# MCU_v2.net
KiCad netlist of a schematic drawn in Altium Designer
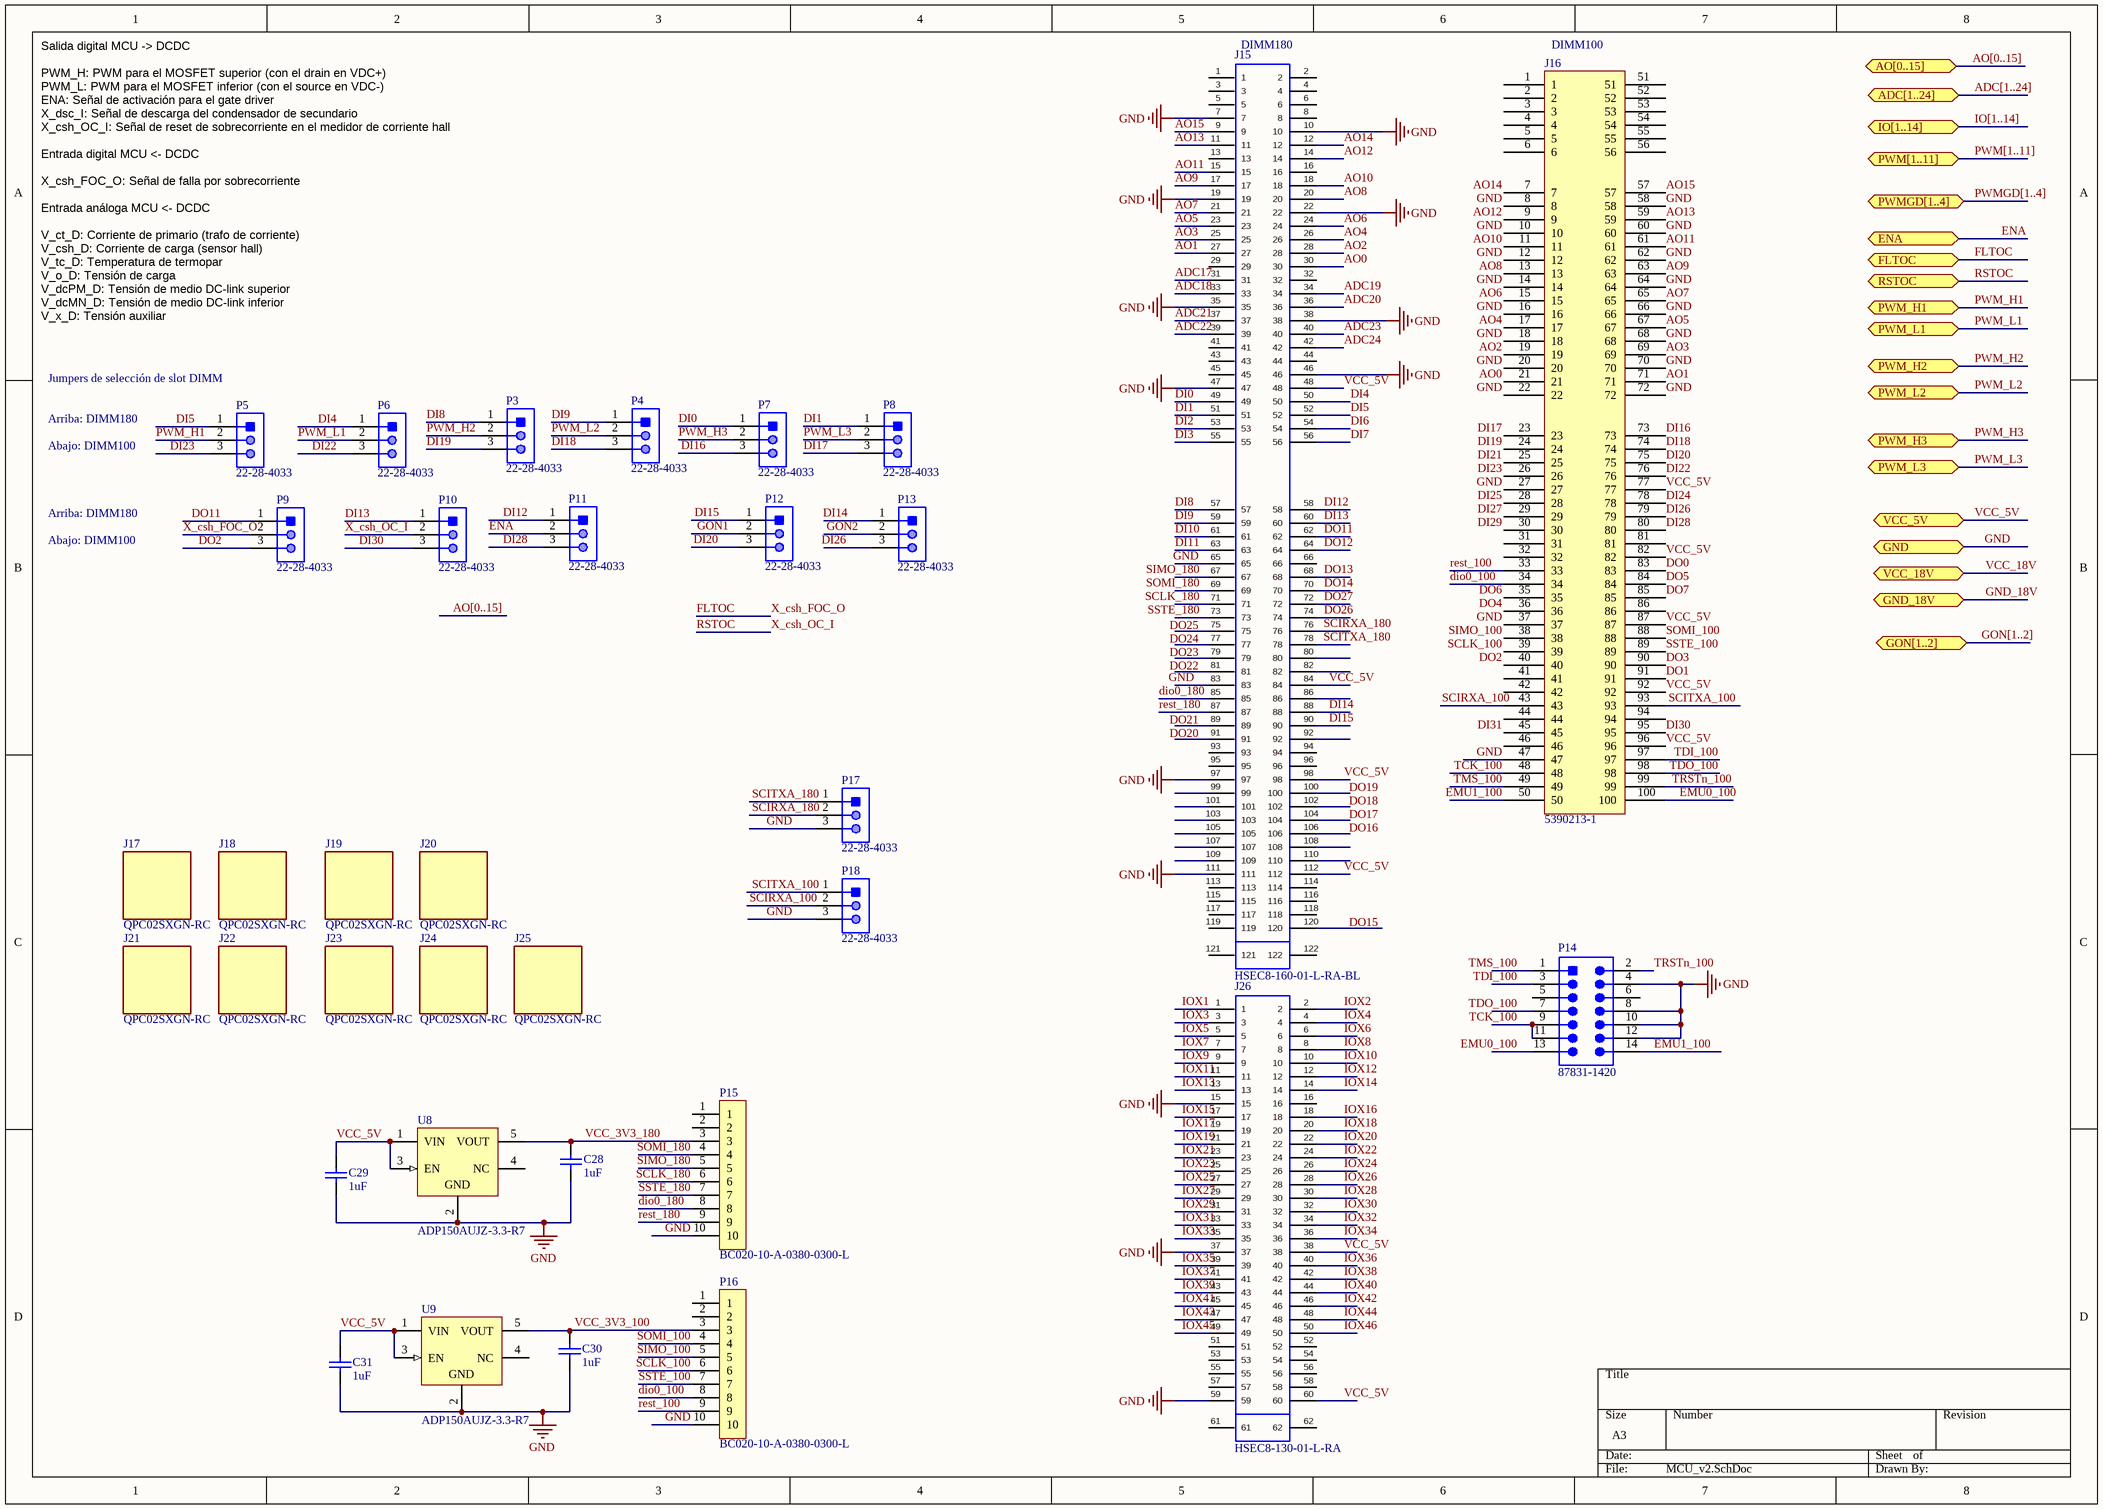
[diagram p0: MCU_v2.SchDoc]

(export (version "E")
  (design (tool "Eeschema 10.0.6"))
  (components
    (comp (ref "C28")
      (value "1uF")
      (footprint "CAPC0603(1608)100_N")
      (description "CAP 1uF 50V ±20% 0603 (1608 Metric) Thickness 1mm SMD")
      (fields (field (name "TOLERANCE") "Â±20%") (field (name "Comment") "CAP 1uF 50V 0603(1608)"))
      (libsource (lib "Altium Content Vault") (part "CAP"))
    )
    (comp (ref "C29")
      (value "1uF")
      (footprint "CAPC0603(1608)100_N")
      (description "CAP 1uF 50V ±20% 0603 (1608 Metric) Thickness 1mm SMD")
      (fields (field (name "TOLERANCE") "Â±20%") (field (name "Comment") "CAP 1uF 50V 0603(1608)"))
      (libsource (lib "Altium Content Vault") (part "CAP"))
    )
    (comp (ref "C30")
      (value "1uF")
      (footprint "CAPC0603(1608)100_N")
      (description "CAP 1uF 50V ±20% 0603 (1608 Metric) Thickness 1mm SMD")
      (fields (field (name "TOLERANCE") "Â±20%") (field (name "Comment") "CAP 1uF 50V 0603(1608)"))
      (libsource (lib "Altium Content Vault") (part "CAP"))
    )
    (comp (ref "C31")
      (value "1uF")
      (footprint "CAPC0603(1608)100_N")
      (description "CAP 1uF 50V ±20% 0603 (1608 Metric) Thickness 1mm SMD")
      (fields (field (name "TOLERANCE") "Â±20%") (field (name "Comment") "CAP 1uF 50V 0603(1608)"))
      (libsource (lib "Altium Content Vault") (part "CAP"))
    )
    (comp (ref "J15")
      (value "HSEC8-160-01-L-RA-BL")
      (footprint "HSEC8-160-01-L-RA-BL")
      (description "Standard Card Edge Connectors 0.80 mm Edge Rate High-Speed Edge Card Connector, Vertical")
      (fields (field (name "MANUFACTURER") "Samtec"))
      (libsource (lib "Altium_Library_POWERLAB") (part "HSEC8-160-01-L-RA-BL"))
    )
    (comp (ref "J16")
      (value "5390213-1")
      (footprint "TE_5390213-1")
      (description "100 Position DIMM DRAM Socket Through Hole")
      (fields (field (name "MF") "TE Connectivity"))
      (libsource (lib "Altium_Library_POWERLAB") (part "5390213-1"))
    )
    (comp (ref "J17")
      (value "QPC02SXGN-RC")
      (footprint "FP-QPC02SXGN-RC-MFG")
      (description "CONN JUMPER SHORTING .100\" GOLD")
      (fields
        (field (name "MANUFACTURER") "Sullins")
        (field (name "OCTOPART") "https://octopart.com/qpc02sxgn-rc-sullins-19878795")
      )
      (libsource (lib "Altium Content Vault") (part "87292ac8601c6cf2061292f5bede09e"))
    )
    (comp (ref "J18")
      (value "QPC02SXGN-RC")
      (footprint "FP-QPC02SXGN-RC-MFG")
      (description "CONN JUMPER SHORTING .100\" GOLD")
      (fields
        (field (name "MANUFACTURER") "Sullins")
        (field (name "OCTOPART") "https://octopart.com/qpc02sxgn-rc-sullins-19878795")
      )
      (libsource (lib "Altium Content Vault") (part "87292ac8601c6cf2061292f5bede09e"))
    )
    (comp (ref "J19")
      (value "QPC02SXGN-RC")
      (footprint "FP-QPC02SXGN-RC-MFG")
      (description "CONN JUMPER SHORTING .100\" GOLD")
      (fields
        (field (name "MANUFACTURER") "Sullins")
        (field (name "OCTOPART") "https://octopart.com/qpc02sxgn-rc-sullins-19878795")
      )
      (libsource (lib "Altium Content Vault") (part "87292ac8601c6cf2061292f5bede09e"))
    )
    (comp (ref "J20")
      (value "QPC02SXGN-RC")
      (footprint "FP-QPC02SXGN-RC-MFG")
      (description "CONN JUMPER SHORTING .100\" GOLD")
      (fields
        (field (name "MANUFACTURER") "Sullins")
        (field (name "OCTOPART") "https://octopart.com/qpc02sxgn-rc-sullins-19878795")
      )
      (libsource (lib "Altium Content Vault") (part "87292ac8601c6cf2061292f5bede09e"))
    )
    (comp (ref "J21")
      (value "QPC02SXGN-RC")
      (footprint "FP-QPC02SXGN-RC-MFG")
      (description "CONN JUMPER SHORTING .100\" GOLD")
      (fields
        (field (name "MANUFACTURER") "Sullins")
        (field (name "OCTOPART") "https://octopart.com/qpc02sxgn-rc-sullins-19878795")
      )
      (libsource (lib "Altium Content Vault") (part "87292ac8601c6cf2061292f5bede09e"))
    )
    (comp (ref "J22")
      (value "QPC02SXGN-RC")
      (footprint "FP-QPC02SXGN-RC-MFG")
      (description "CONN JUMPER SHORTING .100\" GOLD")
      (fields
        (field (name "MANUFACTURER") "Sullins")
        (field (name "OCTOPART") "https://octopart.com/qpc02sxgn-rc-sullins-19878795")
      )
      (libsource (lib "Altium Content Vault") (part "87292ac8601c6cf2061292f5bede09e"))
    )
    (comp (ref "J23")
      (value "QPC02SXGN-RC")
      (footprint "FP-QPC02SXGN-RC-MFG")
      (description "CONN JUMPER SHORTING .100\" GOLD")
      (fields
        (field (name "MANUFACTURER") "Sullins")
        (field (name "OCTOPART") "https://octopart.com/qpc02sxgn-rc-sullins-19878795")
      )
      (libsource (lib "Altium Content Vault") (part "87292ac8601c6cf2061292f5bede09e"))
    )
    (comp (ref "J24")
      (value "QPC02SXGN-RC")
      (footprint "FP-QPC02SXGN-RC-MFG")
      (description "CONN JUMPER SHORTING .100\" GOLD")
      (fields
        (field (name "MANUFACTURER") "Sullins")
        (field (name "OCTOPART") "https://octopart.com/qpc02sxgn-rc-sullins-19878795")
      )
      (libsource (lib "Altium Content Vault") (part "87292ac8601c6cf2061292f5bede09e"))
    )
    (comp (ref "J25")
      (value "QPC02SXGN-RC")
      (footprint "FP-QPC02SXGN-RC-MFG")
      (description "CONN JUMPER SHORTING .100\" GOLD")
      (fields
        (field (name "MANUFACTURER") "Sullins")
        (field (name "OCTOPART") "https://octopart.com/qpc02sxgn-rc-sullins-19878795")
      )
      (libsource (lib "Altium Content Vault") (part "87292ac8601c6cf2061292f5bede09e"))
    )
    (comp (ref "J26")
      (value "HSEC8-130-01-L-RA")
      (footprint "HSEC8-130-01-L-RA")
      (description "SAMTEC - HSEC8-130-01-L-RA - CARD EDGE CONN, DUAL SIDE, 60POS, SMD")
      (fields (field (name "MANUFACTURER") "Samtec"))
      (libsource (lib "Altium_Library_POWERLAB") (part "HSEC8-130-01-L-RA"))
    )
    (comp (ref "P3")
      (value "22-28-4033")
      (footprint "MOLX-22-28-4033_V")
      (description "Male Header, Pitch 2.54 mm, 1 x 3 Position, Height 8.38 mm, Tail Length 3.18 mm, RoHS, Bulk")
      (fields (field (name "MANUFACTURER") "Molex"))
      (libsource (lib "Altium Content Vault") (part "CN-1P-M-R3"))
    )
    (comp (ref "P4")
      (value "22-28-4033")
      (footprint "MOLX-22-28-4033_V")
      (description "Male Header, Pitch 2.54 mm, 1 x 3 Position, Height 8.38 mm, Tail Length 3.18 mm, RoHS, Bulk")
      (fields (field (name "MANUFACTURER") "Molex"))
      (libsource (lib "Altium Content Vault") (part "CN-1P-M-R3"))
    )
    (comp (ref "P5")
      (value "22-28-4033")
      (footprint "MOLX-22-28-4033_V")
      (description "Male Header, Pitch 2.54 mm, 1 x 3 Position, Height 8.38 mm, Tail Length 3.18 mm, RoHS, Bulk")
      (fields (field (name "MANUFACTURER") "Molex"))
      (libsource (lib "Altium Content Vault") (part "CN-1P-M-R3"))
    )
    (comp (ref "P6")
      (value "22-28-4033")
      (footprint "MOLX-22-28-4033_V")
      (description "Male Header, Pitch 2.54 mm, 1 x 3 Position, Height 8.38 mm, Tail Length 3.18 mm, RoHS, Bulk")
      (fields (field (name "MANUFACTURER") "Molex"))
      (libsource (lib "Altium Content Vault") (part "CN-1P-M-R3"))
    )
    (comp (ref "P7")
      (value "22-28-4033")
      (footprint "MOLX-22-28-4033_V")
      (description "Male Header, Pitch 2.54 mm, 1 x 3 Position, Height 8.38 mm, Tail Length 3.18 mm, RoHS, Bulk")
      (fields (field (name "MANUFACTURER") "Molex"))
      (libsource (lib "Altium Content Vault") (part "CN-1P-M-R3"))
    )
    (comp (ref "P8")
      (value "22-28-4033")
      (footprint "MOLX-22-28-4033_V")
      (description "Male Header, Pitch 2.54 mm, 1 x 3 Position, Height 8.38 mm, Tail Length 3.18 mm, RoHS, Bulk")
      (fields (field (name "MANUFACTURER") "Molex"))
      (libsource (lib "Altium Content Vault") (part "CN-1P-M-R3"))
    )
    (comp (ref "P9")
      (value "22-28-4033")
      (footprint "MOLX-22-28-4033_V")
      (description "Male Header, Pitch 2.54 mm, 1 x 3 Position, Height 8.38 mm, Tail Length 3.18 mm, RoHS, Bulk")
      (fields (field (name "MANUFACTURER") "Molex"))
      (libsource (lib "Altium Content Vault") (part "CN-1P-M-R3"))
    )
    (comp (ref "P10")
      (value "22-28-4033")
      (footprint "MOLX-22-28-4033_V")
      (description "Male Header, Pitch 2.54 mm, 1 x 3 Position, Height 8.38 mm, Tail Length 3.18 mm, RoHS, Bulk")
      (fields (field (name "MANUFACTURER") "Molex"))
      (libsource (lib "Altium Content Vault") (part "CN-1P-M-R3"))
    )
    (comp (ref "P11")
      (value "22-28-4033")
      (footprint "MOLX-22-28-4033_V")
      (description "Male Header, Pitch 2.54 mm, 1 x 3 Position, Height 8.38 mm, Tail Length 3.18 mm, RoHS, Bulk")
      (fields (field (name "MANUFACTURER") "Molex"))
      (libsource (lib "Altium Content Vault") (part "CN-1P-M-R3"))
    )
    (comp (ref "P12")
      (value "22-28-4033")
      (footprint "MOLX-22-28-4033_V")
      (description "Male Header, Pitch 2.54 mm, 1 x 3 Position, Height 8.38 mm, Tail Length 3.18 mm, RoHS, Bulk")
      (fields (field (name "MANUFACTURER") "Molex"))
      (libsource (lib "Altium Content Vault") (part "CN-1P-M-R3"))
    )
    (comp (ref "P13")
      (value "22-28-4033")
      (footprint "MOLX-22-28-4033_V")
      (description "Male Header, Pitch 2.54 mm, 1 x 3 Position, Height 8.38 mm, Tail Length 3.18 mm, RoHS, Bulk")
      (fields (field (name "MANUFACTURER") "Molex"))
      (libsource (lib "Altium Content Vault") (part "CN-1P-M-R3"))
    )
    (comp (ref "P14")
      (value "87831-1420")
      (footprint "MOLEX-87831-1420_V")
      (description "Header, Pitch 2 mm, 2 x 7 Position, Height 6.4 mm, Tail Length 2.5 mm, -55 to 105 degC, RoHS, Tube")
      (fields (field (name "MANUFACTURER") "Molex"))
      (libsource (lib "Altium Content Vault") (part "CN-2P-M-R14"))
    )
    (comp (ref "P15")
      (value "BC020-10-A-0380-0300-L")
      (footprint "BC020-10-A-0380-0300-L")
      (fields (field (name "MANUFACTURER") "Global Connector Technology"))
      (libsource (lib "Altium_Library_POWERLAB") (part "BC020-10-A-0380-0300-L"))
    )
    (comp (ref "P16")
      (value "BC020-10-A-0380-0300-L")
      (footprint "BC020-10-A-0380-0300-L")
      (fields (field (name "MANUFACTURER") "Global Connector Technology"))
      (libsource (lib "Altium_Library_POWERLAB") (part "BC020-10-A-0380-0300-L"))
    )
    (comp (ref "P17")
      (value "22-28-4033")
      (footprint "MOLX-22-28-4033_V")
      (description "Male Header, Pitch 2.54 mm, 1 x 3 Position, Height 8.38 mm, Tail Length 3.18 mm, RoHS, Bulk")
      (fields (field (name "MANUFACTURER") "Molex"))
      (libsource (lib "Altium Content Vault") (part "CN-1P-M-R3"))
    )
    (comp (ref "P18")
      (value "22-28-4033")
      (footprint "MOLX-22-28-4033_V")
      (description "Male Header, Pitch 2.54 mm, 1 x 3 Position, Height 8.38 mm, Tail Length 3.18 mm, RoHS, Bulk")
      (fields (field (name "MANUFACTURER") "Molex"))
      (libsource (lib "Altium Content Vault") (part "CN-1P-M-R3"))
    )
    (comp (ref "U8")
      (value "ADP150AUJZ-3.3-R7")
      (footprint "ADI-UJ-5_M")
      (fields (field (name "MANUFACTURER") "Analog Devices"))
      (libsource (lib "Altium Content Vault") (part "ADI-ADP1XX-UJ-5"))
    )
    (comp (ref "U9")
      (value "ADP150AUJZ-3.3-R7")
      (footprint "ADI-UJ-5_M")
      (fields (field (name "MANUFACTURER") "Analog Devices"))
      (libsource (lib "Altium Content Vault") (part "ADI-ADP1XX-UJ-5"))
    )
  )
  (nets
    (net (code "46") (name "/ADC17") (class "Default")
      (node (ref "J15") (pin "31") (pinfunction "31_31") (pintype "passive"))
    )
    (net (code "47") (name "/ADC18") (class "Default")
      (node (ref "J15") (pin "33") (pinfunction "33_33") (pintype "passive"))
    )
    (net (code "48") (name "/ADC19") (class "Default")
      (node (ref "J15") (pin "34") (pinfunction "34_34") (pintype "passive"))
    )
    (net (code "49") (name "/ADC20") (class "Default")
      (node (ref "J15") (pin "36") (pinfunction "36_36") (pintype "passive"))
    )
    (net (code "50") (name "/ADC21") (class "Default")
      (node (ref "J15") (pin "37") (pinfunction "37_37") (pintype "passive"))
    )
    (net (code "51") (name "/ADC22") (class "Default")
      (node (ref "J15") (pin "39") (pinfunction "39_39") (pintype "passive"))
    )
    (net (code "52") (name "/ADC23") (class "Default")
      (node (ref "J15") (pin "40") (pinfunction "40_40") (pintype "passive"))
    )
    (net (code "53") (name "/ADC24") (class "Default")
      (node (ref "J15") (pin "42") (pinfunction "42_42") (pintype "passive"))
    )
    (net (code "55") (name "/AO0") (class "Default")
      (node (ref "J15") (pin "30") (pinfunction "30_30") (pintype "passive"))
      (node (ref "J16") (pin "21") (pinfunction "21_21") (pintype "power_in"))
    )
    (net (code "56") (name "/AO1") (class "Default")
      (node (ref "J15") (pin "27") (pinfunction "27_27") (pintype "passive"))
      (node (ref "J16") (pin "71") (pinfunction "71_71") (pintype "power_in"))
    )
    (net (code "57") (name "/AO2") (class "Default")
      (node (ref "J15") (pin "28") (pinfunction "28_28") (pintype "passive"))
      (node (ref "J16") (pin "19") (pinfunction "19_19") (pintype "power_in"))
    )
    (net (code "58") (name "/AO3") (class "Default")
      (node (ref "J15") (pin "25") (pinfunction "25_25") (pintype "passive"))
      (node (ref "J16") (pin "69") (pinfunction "69_69") (pintype "power_in"))
    )
    (net (code "59") (name "/AO4") (class "Default")
      (node (ref "J15") (pin "26") (pinfunction "26_26") (pintype "passive"))
      (node (ref "J16") (pin "17") (pinfunction "17_17") (pintype "power_in"))
    )
    (net (code "60") (name "/AO5") (class "Default")
      (node (ref "J15") (pin "23") (pinfunction "23_23") (pintype "passive"))
      (node (ref "J16") (pin "67") (pinfunction "67_67") (pintype "power_in"))
    )
    (net (code "61") (name "/AO6") (class "Default")
      (node (ref "J15") (pin "24") (pinfunction "24_24") (pintype "passive"))
      (node (ref "J16") (pin "15") (pinfunction "15_15") (pintype "power_in"))
    )
    (net (code "62") (name "/AO7") (class "Default")
      (node (ref "J15") (pin "21") (pinfunction "21_21") (pintype "passive"))
      (node (ref "J16") (pin "65") (pinfunction "65_65") (pintype "power_in"))
    )
    (net (code "63") (name "/AO8") (class "Default")
      (node (ref "J15") (pin "20") (pinfunction "20_20") (pintype "passive"))
      (node (ref "J16") (pin "13") (pinfunction "13_13") (pintype "power_in"))
    )
    (net (code "64") (name "/AO9") (class "Default")
      (node (ref "J15") (pin "17") (pinfunction "17_17") (pintype "passive"))
      (node (ref "J16") (pin "63") (pinfunction "63_63") (pintype "power_in"))
    )
    (net (code "65") (name "/AO10") (class "Default")
      (node (ref "J15") (pin "18") (pinfunction "18_18") (pintype "passive"))
      (node (ref "J16") (pin "11") (pinfunction "11_11") (pintype "power_in"))
    )
    (net (code "66") (name "/AO11") (class "Default")
      (node (ref "J15") (pin "15") (pinfunction "15_15") (pintype "passive"))
      (node (ref "J16") (pin "61") (pinfunction "61_61") (pintype "power_in"))
    )
    (net (code "67") (name "/AO12") (class "Default")
      (node (ref "J15") (pin "14") (pinfunction "14_14") (pintype "passive"))
      (node (ref "J16") (pin "9") (pinfunction "9_9") (pintype "power_in"))
    )
    (net (code "68") (name "/AO13") (class "Default")
      (node (ref "J15") (pin "11") (pinfunction "11_11") (pintype "passive"))
      (node (ref "J16") (pin "59") (pinfunction "59_59") (pintype "power_in"))
    )
    (net (code "69") (name "/AO14") (class "Default")
      (node (ref "J15") (pin "12") (pinfunction "12_12") (pintype "passive"))
      (node (ref "J16") (pin "7") (pinfunction "7_7") (pintype "power_in"))
    )
    (net (code "70") (name "/AO15") (class "Default")
      (node (ref "J15") (pin "9") (pinfunction "9_9") (pintype "passive"))
      (node (ref "J16") (pin "57") (pinfunction "57_57") (pintype "power_in"))
    )
    (net (code "72") (name "/DI0") (class "Default")
      (node (ref "J15") (pin "49") (pinfunction "49_49") (pintype "passive"))
      (node (ref "P7") (pin "1") (pinfunction "1_1") (pintype "passive"))
    )
    (net (code "73") (name "/DI1") (class "Default")
      (node (ref "J15") (pin "51") (pinfunction "51_51") (pintype "passive"))
      (node (ref "P8") (pin "1") (pinfunction "1_1") (pintype "passive"))
    )
    (net (code "74") (name "/DI2") (class "Default")
      (node (ref "J15") (pin "53") (pinfunction "53_53") (pintype "passive"))
    )
    (net (code "75") (name "/DI3") (class "Default")
      (node (ref "J15") (pin "55") (pinfunction "55_55") (pintype "passive"))
    )
    (net (code "76") (name "/DI4") (class "Default")
      (node (ref "J15") (pin "50") (pinfunction "50_50") (pintype "passive"))
      (node (ref "P6") (pin "1") (pinfunction "1_1") (pintype "passive"))
    )
    (net (code "77") (name "/DI5") (class "Default")
      (node (ref "J15") (pin "52") (pinfunction "52_52") (pintype "passive"))
      (node (ref "P5") (pin "1") (pinfunction "1_1") (pintype "passive"))
    )
    (net (code "78") (name "/DI6") (class "Default")
      (node (ref "J15") (pin "54") (pinfunction "54_54") (pintype "passive"))
    )
    (net (code "79") (name "/DI7") (class "Default")
      (node (ref "J15") (pin "56") (pinfunction "56_56") (pintype "passive"))
    )
    (net (code "80") (name "/DI8") (class "Default")
      (node (ref "J15") (pin "57") (pinfunction "57_57") (pintype "passive"))
      (node (ref "P3") (pin "1") (pinfunction "1_1") (pintype "passive"))
    )
    (net (code "81") (name "/DI9") (class "Default")
      (node (ref "J15") (pin "59") (pinfunction "59_59") (pintype "passive"))
      (node (ref "P4") (pin "1") (pinfunction "1_1") (pintype "passive"))
    )
    (net (code "82") (name "/DI10") (class "Default")
      (node (ref "J15") (pin "61") (pinfunction "61_61") (pintype "passive"))
    )
    (net (code "83") (name "/DI11") (class "Default")
      (node (ref "J15") (pin "63") (pinfunction "63_63") (pintype "passive"))
    )
    (net (code "84") (name "/DI12") (class "Default")
      (node (ref "J15") (pin "58") (pinfunction "58_58") (pintype "passive"))
      (node (ref "P11") (pin "1") (pinfunction "1_1") (pintype "passive"))
    )
    (net (code "85") (name "/DI13") (class "Default")
      (node (ref "J15") (pin "60") (pinfunction "60_60") (pintype "passive"))
      (node (ref "P10") (pin "1") (pinfunction "1_1") (pintype "passive"))
    )
    (net (code "86") (name "/DI14") (class "Default")
      (node (ref "J15") (pin "88") (pinfunction "88_88") (pintype "passive"))
      (node (ref "P13") (pin "1") (pinfunction "1_1") (pintype "passive"))
    )
    (net (code "87") (name "/DI15") (class "Default")
      (node (ref "J15") (pin "90") (pinfunction "90_90") (pintype "passive"))
      (node (ref "P12") (pin "1") (pinfunction "1_1") (pintype "passive"))
    )
    (net (code "88") (name "/DI16") (class "Default")
      (node (ref "J16") (pin "73") (pinfunction "73_73") (pintype "power_in"))
      (node (ref "P7") (pin "3") (pinfunction "3_3") (pintype "passive"))
    )
    (net (code "89") (name "/DI17") (class "Default")
      (node (ref "J16") (pin "23") (pinfunction "23_23") (pintype "power_in"))
      (node (ref "P8") (pin "3") (pinfunction "3_3") (pintype "passive"))
    )
    (net (code "90") (name "/DI18") (class "Default")
      (node (ref "J16") (pin "74") (pinfunction "74_74") (pintype "power_in"))
      (node (ref "P4") (pin "3") (pinfunction "3_3") (pintype "passive"))
    )
    (net (code "91") (name "/DI19") (class "Default")
      (node (ref "J16") (pin "24") (pinfunction "24_24") (pintype "power_in"))
      (node (ref "P3") (pin "3") (pinfunction "3_3") (pintype "passive"))
    )
    (net (code "92") (name "/DI20") (class "Default")
      (node (ref "J16") (pin "75") (pinfunction "75_75") (pintype "power_in"))
      (node (ref "P12") (pin "3") (pinfunction "3_3") (pintype "passive"))
    )
    (net (code "93") (name "/DI21") (class "Default")
      (node (ref "J16") (pin "25") (pinfunction "25_25") (pintype "power_in"))
    )
    (net (code "94") (name "/DI22") (class "Default")
      (node (ref "J16") (pin "76") (pinfunction "76_76") (pintype "power_in"))
      (node (ref "P6") (pin "3") (pinfunction "3_3") (pintype "passive"))
    )
    (net (code "95") (name "/DI23") (class "Default")
      (node (ref "J16") (pin "26") (pinfunction "26_26") (pintype "power_in"))
      (node (ref "P5") (pin "3") (pinfunction "3_3") (pintype "passive"))
    )
    (net (code "96") (name "/DI24") (class "Default")
      (node (ref "J16") (pin "78") (pinfunction "78_78") (pintype "power_in"))
    )
    (net (code "97") (name "/DI25") (class "Default")
      (node (ref "J16") (pin "28") (pinfunction "28_28") (pintype "power_in"))
    )
    (net (code "98") (name "/DI26") (class "Default")
      (node (ref "J16") (pin "79") (pinfunction "79_79") (pintype "power_in"))
      (node (ref "P13") (pin "3") (pinfunction "3_3") (pintype "passive"))
    )
    (net (code "99") (name "/DI27") (class "Default")
      (node (ref "J16") (pin "29") (pinfunction "29_29") (pintype "power_in"))
    )
    (net (code "100") (name "/DI28") (class "Default")
      (node (ref "J16") (pin "80") (pinfunction "80_80") (pintype "power_in"))
      (node (ref "P11") (pin "3") (pinfunction "3_3") (pintype "passive"))
    )
    (net (code "101") (name "/DI29") (class "Default")
      (node (ref "J16") (pin "30") (pinfunction "30_30") (pintype "power_in"))
    )
    (net (code "102") (name "/DI30") (class "Default")
      (node (ref "J16") (pin "95") (pinfunction "95_95") (pintype "power_in"))
      (node (ref "P10") (pin "3") (pinfunction "3_3") (pintype "passive"))
    )
    (net (code "103") (name "/DI31") (class "Default")
      (node (ref "J16") (pin "45") (pinfunction "45_45") (pintype "power_in"))
    )
    (net (code "104") (name "/DO0") (class "Default")
      (node (ref "J16") (pin "83") (pinfunction "83_83") (pintype "power_in"))
    )
    (net (code "105") (name "/DO1") (class "Default")
      (node (ref "J16") (pin "91") (pinfunction "91_91") (pintype "power_in"))
    )
    (net (code "106") (name "/DO2") (class "Default")
      (node (ref "J16") (pin "40") (pinfunction "40_40") (pintype "power_in"))
      (node (ref "P9") (pin "3") (pinfunction "3_3") (pintype "passive"))
    )
    (net (code "107") (name "/DO3") (class "Default")
      (node (ref "J16") (pin "90") (pinfunction "90_90") (pintype "power_in"))
    )
    (net (code "108") (name "/DO4") (class "Default")
      (node (ref "J16") (pin "36") (pinfunction "36_36") (pintype "power_in"))
    )
    (net (code "109") (name "/DO5") (class "Default")
      (node (ref "J16") (pin "84") (pinfunction "84_84") (pintype "power_in"))
    )
    (net (code "110") (name "/DO6") (class "Default")
      (node (ref "J16") (pin "35") (pinfunction "35_35") (pintype "power_in"))
    )
    (net (code "111") (name "/DO7") (class "Default")
      (node (ref "J16") (pin "85") (pinfunction "85_85") (pintype "power_in"))
    )
    (net (code "112") (name "/DO11") (class "Default")
      (node (ref "J15") (pin "62") (pinfunction "62_62") (pintype "passive"))
      (node (ref "P9") (pin "1") (pinfunction "1_1") (pintype "passive"))
    )
    (net (code "113") (name "/DO12") (class "Default")
      (node (ref "J15") (pin "64") (pinfunction "64_64") (pintype "passive"))
    )
    (net (code "114") (name "/DO13") (class "Default")
      (node (ref "J15") (pin "68") (pinfunction "68_68") (pintype "passive"))
    )
    (net (code "115") (name "/DO14") (class "Default")
      (node (ref "J15") (pin "70") (pinfunction "70_70") (pintype "passive"))
    )
    (net (code "127") (name "/DO26") (class "Default")
      (node (ref "J15") (pin "74") (pinfunction "74_74") (pintype "passive"))
    )
    (net (code "128") (name "/DO27") (class "Default")
      (node (ref "J15") (pin "72") (pinfunction "72_72") (pintype "passive"))
    )
    (net (code "129") (name "/EMU0_100") (class "Default")
      (node (ref "J16") (pin "100") (pinfunction "100_100") (pintype "power_in"))
      (node (ref "P14") (pin "13") (pinfunction "13_13") (pintype "passive"))
    )
    (net (code "130") (name "/EMU1_100") (class "Default")
      (node (ref "J16") (pin "50") (pinfunction "50_50") (pintype "power_in"))
      (node (ref "P14") (pin "14") (pinfunction "14_14") (pintype "passive"))
    )
    (net (code "131") (name "/ENA") (class "Default")
      (node (ref "P11") (pin "2") (pinfunction "2_2") (pintype "passive"))
    )
    (net (code "132") (name "/FLTOC") (class "Default")
      (node (ref "P9") (pin "2") (pinfunction "2_2") (pintype "passive"))
    )
    (net (code "134") (name "/GON1") (class "Default")
      (node (ref "P12") (pin "2") (pinfunction "2_2") (pintype "passive"))
    )
    (net (code "135") (name "/GON2") (class "Default")
      (node (ref "P13") (pin "2") (pinfunction "2_2") (pintype "passive"))
    )
    (net (code "137") (name "/IOX1") (class "Default")
      (node (ref "J26") (pin "1") (pinfunction "1_1") (pintype "passive"))
    )
    (net (code "138") (name "/IOX2") (class "Default")
      (node (ref "J26") (pin "2") (pinfunction "2_2") (pintype "passive"))
    )
    (net (code "139") (name "/IOX3") (class "Default")
      (node (ref "J26") (pin "3") (pinfunction "3_3") (pintype "passive"))
    )
    (net (code "140") (name "/IOX4") (class "Default")
      (node (ref "J26") (pin "4") (pinfunction "4_4") (pintype "passive"))
    )
    (net (code "141") (name "/IOX5") (class "Default")
      (node (ref "J26") (pin "5") (pinfunction "5_5") (pintype "passive"))
    )
    (net (code "142") (name "/IOX6") (class "Default")
      (node (ref "J26") (pin "6") (pinfunction "6_6") (pintype "passive"))
    )
    (net (code "143") (name "/IOX7") (class "Default")
      (node (ref "J26") (pin "7") (pinfunction "7_7") (pintype "passive"))
    )
    (net (code "144") (name "/IOX8") (class "Default")
      (node (ref "J26") (pin "8") (pinfunction "8_8") (pintype "passive"))
    )
    (net (code "145") (name "/IOX9") (class "Default")
      (node (ref "J26") (pin "9") (pinfunction "9_9") (pintype "passive"))
    )
    (net (code "146") (name "/IOX10") (class "Default")
      (node (ref "J26") (pin "10") (pinfunction "10_10") (pintype "passive"))
    )
    (net (code "147") (name "/IOX11") (class "Default")
      (node (ref "J26") (pin "11") (pinfunction "11_11") (pintype "passive"))
    )
    (net (code "148") (name "/IOX12") (class "Default")
      (node (ref "J26") (pin "12") (pinfunction "12_12") (pintype "passive"))
    )
    (net (code "149") (name "/IOX13") (class "Default")
      (node (ref "J26") (pin "13") (pinfunction "13_13") (pintype "passive"))
    )
    (net (code "150") (name "/IOX14") (class "Default")
      (node (ref "J26") (pin "14") (pinfunction "14_14") (pintype "passive"))
    )
    (net (code "151") (name "/IOX15") (class "Default")
      (node (ref "J26") (pin "17") (pinfunction "17_17") (pintype "passive"))
    )
    (net (code "152") (name "/IOX16") (class "Default")
      (node (ref "J26") (pin "18") (pinfunction "18_18") (pintype "passive"))
    )
    (net (code "153") (name "/IOX17") (class "Default")
      (node (ref "J26") (pin "19") (pinfunction "19_19") (pintype "passive"))
    )
    (net (code "154") (name "/IOX18") (class "Default")
      (node (ref "J26") (pin "20") (pinfunction "20_20") (pintype "passive"))
    )
    (net (code "155") (name "/IOX19") (class "Default")
      (node (ref "J26") (pin "21") (pinfunction "21_21") (pintype "passive"))
    )
    (net (code "156") (name "/IOX20") (class "Default")
      (node (ref "J26") (pin "22") (pinfunction "22_22") (pintype "passive"))
    )
    (net (code "157") (name "/IOX21") (class "Default")
      (node (ref "J26") (pin "23") (pinfunction "23_23") (pintype "passive"))
    )
    (net (code "158") (name "/IOX22") (class "Default")
      (node (ref "J26") (pin "24") (pinfunction "24_24") (pintype "passive"))
    )
    (net (code "159") (name "/IOX23") (class "Default")
      (node (ref "J26") (pin "25") (pinfunction "25_25") (pintype "passive"))
    )
    (net (code "160") (name "/IOX24") (class "Default")
      (node (ref "J26") (pin "26") (pinfunction "26_26") (pintype "passive"))
    )
    (net (code "161") (name "/IOX25") (class "Default")
      (node (ref "J26") (pin "27") (pinfunction "27_27") (pintype "passive"))
    )
    (net (code "162") (name "/IOX26") (class "Default")
      (node (ref "J26") (pin "28") (pinfunction "28_28") (pintype "passive"))
    )
    (net (code "163") (name "/IOX27") (class "Default")
      (node (ref "J26") (pin "29") (pinfunction "29_29") (pintype "passive"))
    )
    (net (code "164") (name "/IOX28") (class "Default")
      (node (ref "J26") (pin "30") (pinfunction "30_30") (pintype "passive"))
    )
    (net (code "165") (name "/IOX29") (class "Default")
      (node (ref "J26") (pin "31") (pinfunction "31_31") (pintype "passive"))
    )
    (net (code "166") (name "/IOX30") (class "Default")
      (node (ref "J26") (pin "32") (pinfunction "32_32") (pintype "passive"))
    )
    (net (code "167") (name "/IOX31") (class "Default")
      (node (ref "J26") (pin "33") (pinfunction "33_33") (pintype "passive"))
    )
    (net (code "168") (name "/IOX32") (class "Default")
      (node (ref "J26") (pin "34") (pinfunction "34_34") (pintype "passive"))
    )
    (net (code "169") (name "/IOX33") (class "Default")
      (node (ref "J26") (pin "35") (pinfunction "35_35") (pintype "passive"))
    )
    (net (code "170") (name "/IOX34") (class "Default")
      (node (ref "J26") (pin "36") (pinfunction "36_36") (pintype "passive"))
    )
    (net (code "171") (name "/IOX35") (class "Default")
      (node (ref "J26") (pin "39") (pinfunction "39_39") (pintype "passive"))
    )
    (net (code "172") (name "/IOX36") (class "Default")
      (node (ref "J26") (pin "40") (pinfunction "40_40") (pintype "passive"))
    )
    (net (code "173") (name "/IOX37") (class "Default")
      (node (ref "J26") (pin "41") (pinfunction "41_41") (pintype "passive"))
    )
    (net (code "174") (name "/IOX38") (class "Default")
      (node (ref "J26") (pin "42") (pinfunction "42_42") (pintype "passive"))
    )
    (net (code "175") (name "/IOX39") (class "Default")
      (node (ref "J26") (pin "43") (pinfunction "43_43") (pintype "passive"))
    )
    (net (code "176") (name "/IOX40") (class "Default")
      (node (ref "J26") (pin "44") (pinfunction "44_44") (pintype "passive"))
    )
    (net (code "177") (name "/IOX41") (class "Default")
      (node (ref "J26") (pin "45") (pinfunction "45_45") (pintype "passive"))
    )
    (net (code "178") (name "/IOX42") (class "Default")
      (node (ref "J26") (pin "46") (pinfunction "46_46") (pintype "passive"))
    )
    (net (code "179") (name "/IOX43") (class "Default")
      (node (ref "J26") (pin "47") (pinfunction "47_47") (pintype "passive"))
    )
    (net (code "180") (name "/IOX44") (class "Default")
      (node (ref "J26") (pin "48") (pinfunction "48_48") (pintype "passive"))
    )
    (net (code "181") (name "/IOX45") (class "Default")
      (node (ref "J26") (pin "49") (pinfunction "49_49") (pintype "passive"))
    )
    (net (code "182") (name "/IOX46") (class "Default")
      (node (ref "J26") (pin "50") (pinfunction "50_50") (pintype "passive"))
    )
    (net (code "186") (name "/PWM_H1") (class "Default")
      (node (ref "P5") (pin "2") (pinfunction "2_2") (pintype "passive"))
    )
    (net (code "187") (name "/PWM_H2") (class "Default")
      (node (ref "P3") (pin "2") (pinfunction "2_2") (pintype "passive"))
    )
    (net (code "188") (name "/PWM_H3") (class "Default")
      (node (ref "P7") (pin "2") (pinfunction "2_2") (pintype "passive"))
    )
    (net (code "189") (name "/PWM_L1") (class "Default")
      (node (ref "P6") (pin "2") (pinfunction "2_2") (pintype "passive"))
    )
    (net (code "190") (name "/PWM_L2") (class "Default")
      (node (ref "P4") (pin "2") (pinfunction "2_2") (pintype "passive"))
    )
    (net (code "191") (name "/PWM_L3") (class "Default")
      (node (ref "P8") (pin "2") (pinfunction "2_2") (pintype "passive"))
    )
    (net (code "192") (name "/RSTOC") (class "Default")
      (node (ref "P10") (pin "2") (pinfunction "2_2") (pintype "passive"))
    )
    (net (code "193") (name "/SCIRXA_100") (class "Default")
      (node (ref "J16") (pin "43") (pinfunction "43_43") (pintype "power_in"))
      (node (ref "P18") (pin "2") (pinfunction "2_2") (pintype "passive"))
    )
    (net (code "194") (name "/SCIRXA_180") (class "Default")
      (node (ref "J15") (pin "76") (pinfunction "76_76") (pintype "passive"))
      (node (ref "P17") (pin "2") (pinfunction "2_2") (pintype "passive"))
    )
    (net (code "195") (name "/SCITXA_100") (class "Default")
      (node (ref "J16") (pin "93") (pinfunction "93_93") (pintype "power_in"))
      (node (ref "P18") (pin "1") (pinfunction "1_1") (pintype "passive"))
    )
    (net (code "196") (name "/SCITXA_180") (class "Default")
      (node (ref "J15") (pin "78") (pinfunction "78_78") (pintype "passive"))
      (node (ref "P17") (pin "1") (pinfunction "1_1") (pintype "passive"))
    )
    (net (code "197") (name "/SCLK_100") (class "Default")
      (node (ref "J16") (pin "39") (pinfunction "39_39") (pintype "power_in"))
      (node (ref "P16") (pin "6") (pinfunction "6_6") (pintype "passive"))
    )
    (net (code "198") (name "/SCLK_180") (class "Default")
      (node (ref "J15") (pin "71") (pinfunction "71_71") (pintype "passive"))
      (node (ref "P15") (pin "6") (pinfunction "6_6") (pintype "passive"))
    )
    (net (code "199") (name "/SIMO_100") (class "Default")
      (node (ref "J16") (pin "38") (pinfunction "38_38") (pintype "power_in"))
      (node (ref "P16") (pin "5") (pinfunction "5_5") (pintype "passive"))
    )
    (net (code "200") (name "/SIMO_180") (class "Default")
      (node (ref "J15") (pin "67") (pinfunction "67_67") (pintype "passive"))
      (node (ref "P15") (pin "5") (pinfunction "5_5") (pintype "passive"))
    )
    (net (code "201") (name "/SOMI_100") (class "Default")
      (node (ref "J16") (pin "88") (pinfunction "88_88") (pintype "power_in"))
      (node (ref "P16") (pin "4") (pinfunction "4_4") (pintype "passive"))
    )
    (net (code "202") (name "/SOMI_180") (class "Default")
      (node (ref "J15") (pin "69") (pinfunction "69_69") (pintype "passive"))
      (node (ref "P15") (pin "4") (pinfunction "4_4") (pintype "passive"))
    )
    (net (code "203") (name "/SSTE_100") (class "Default")
      (node (ref "J16") (pin "89") (pinfunction "89_89") (pintype "power_in"))
      (node (ref "P16") (pin "7") (pinfunction "7_7") (pintype "passive"))
    )
    (net (code "204") (name "/SSTE_180") (class "Default")
      (node (ref "J15") (pin "73") (pinfunction "73_73") (pintype "passive"))
      (node (ref "P15") (pin "7") (pinfunction "7_7") (pintype "passive"))
    )
    (net (code "205") (name "/TCK_100") (class "Default")
      (node (ref "J16") (pin "48") (pinfunction "48_48") (pintype "power_in"))
      (node (ref "P14") (pin "11") (pinfunction "11_11") (pintype "passive"))
      (node (ref "P14") (pin "9") (pinfunction "9_9") (pintype "passive"))
    )
    (net (code "206") (name "/TDI_100") (class "Default")
      (node (ref "J16") (pin "97") (pinfunction "97_97") (pintype "power_in"))
      (node (ref "P14") (pin "3") (pinfunction "3_3") (pintype "passive"))
    )
    (net (code "207") (name "/TDO_100") (class "Default")
      (node (ref "J16") (pin "98") (pinfunction "98_98") (pintype "power_in"))
      (node (ref "P14") (pin "7") (pinfunction "7_7") (pintype "passive"))
    )
    (net (code "208") (name "/TMS_100") (class "Default")
      (node (ref "J16") (pin "49") (pinfunction "49_49") (pintype "power_in"))
      (node (ref "P14") (pin "1") (pinfunction "1_1") (pintype "passive"))
    )
    (net (code "209") (name "/TRSTn_100") (class "Default")
      (node (ref "J16") (pin "99") (pinfunction "99_99") (pintype "power_in"))
      (node (ref "P14") (pin "2") (pinfunction "2_2") (pintype "passive"))
    )
    (net (code "210") (name "/VCC_3V3_100") (class "Default")
      (node (ref "C30") (pin "2") (pinfunction "2_2") (pintype "passive"))
      (node (ref "P16") (pin "3") (pinfunction "3_3") (pintype "passive"))
      (node (ref "U9") (pin "5") (pinfunction "VOUT_5") (pintype "power_in"))
    )
    (net (code "211") (name "/VCC_3V3_180") (class "Default")
      (node (ref "C28") (pin "2") (pinfunction "2_2") (pintype "passive"))
      (node (ref "P15") (pin "3") (pinfunction "3_3") (pintype "passive"))
      (node (ref "U8") (pin "5") (pinfunction "VOUT_5") (pintype "power_in"))
    )
    (net (code "212") (name "/VCC_5V") (class "Default")
      (node (ref "C29") (pin "2") (pinfunction "2_2") (pintype "passive"))
      (node (ref "C31") (pin "2") (pinfunction "2_2") (pintype "passive"))
      (node (ref "J15") (pin "112") (pinfunction "112_112") (pintype "passive"))
      (node (ref "J15") (pin "48") (pinfunction "48_48") (pintype "passive"))
      (node (ref "J15") (pin "84") (pinfunction "84_84") (pintype "passive"))
      (node (ref "J15") (pin "98") (pinfunction "98_98") (pintype "passive"))
      (node (ref "J16") (pin "77") (pinfunction "77_77") (pintype "power_in"))
      (node (ref "J16") (pin "82") (pinfunction "82_82") (pintype "power_in"))
      (node (ref "J16") (pin "87") (pinfunction "87_87") (pintype "power_in"))
      (node (ref "J16") (pin "92") (pinfunction "92_92") (pintype "power_in"))
      (node (ref "J16") (pin "96") (pinfunction "96_96") (pintype "power_in"))
      (node (ref "J26") (pin "38") (pinfunction "38_38") (pintype "passive"))
      (node (ref "J26") (pin "60") (pinfunction "60_60") (pintype "passive"))
      (node (ref "U8") (pin "1") (pinfunction "VIN_1") (pintype "power_in"))
      (node (ref "U8") (pin "3") (pinfunction "EN_3") (pintype "input"))
      (node (ref "U9") (pin "1") (pinfunction "VIN_1") (pintype "power_in"))
      (node (ref "U9") (pin "3") (pinfunction "EN_3") (pintype "input"))
    )
    (net (code "214") (name "/dio0_100") (class "Default")
      (node (ref "J16") (pin "34") (pinfunction "34_34") (pintype "power_in"))
      (node (ref "P16") (pin "8") (pinfunction "8_8") (pintype "passive"))
    )
    (net (code "215") (name "/dio0_180") (class "Default")
      (node (ref "J15") (pin "85") (pinfunction "85_85") (pintype "passive"))
      (node (ref "P15") (pin "8") (pinfunction "8_8") (pintype "passive"))
    )
    (net (code "216") (name "/rest_100") (class "Default")
      (node (ref "J16") (pin "33") (pinfunction "33_33") (pintype "power_in"))
      (node (ref "P16") (pin "9") (pinfunction "9_9") (pintype "passive"))
    )
    (net (code "217") (name "/rest_180") (class "Default")
      (node (ref "J15") (pin "87") (pinfunction "87_87") (pintype "passive"))
      (node (ref "P15") (pin "9") (pinfunction "9_9") (pintype "passive"))
    )
    (net (code "218") (name "GND") (class "Default")
      (node (ref "C28") (pin "1") (pinfunction "1_1") (pintype "passive"))
      (node (ref "C29") (pin "1") (pinfunction "1_1") (pintype "passive"))
      (node (ref "C30") (pin "1") (pinfunction "1_1") (pintype "passive"))
      (node (ref "C31") (pin "1") (pinfunction "1_1") (pintype "passive"))
      (node (ref "J15") (pin "10") (pinfunction "10_10") (pintype "passive"))
      (node (ref "J15") (pin "111") (pinfunction "111_111") (pintype "passive"))
      (node (ref "J15") (pin "19") (pinfunction "19_19") (pintype "passive"))
      (node (ref "J15") (pin "22") (pinfunction "22_22") (pintype "passive"))
      (node (ref "J15") (pin "35") (pinfunction "35_35") (pintype "passive"))
      (node (ref "J15") (pin "38") (pinfunction "38_38") (pintype "passive"))
      (node (ref "J15") (pin "46") (pinfunction "46_46") (pintype "passive"))
      (node (ref "J15") (pin "47") (pinfunction "47_47") (pintype "passive"))
      (node (ref "J15") (pin "65") (pinfunction "65_65") (pintype "passive"))
      (node (ref "J15") (pin "7") (pinfunction "7_7") (pintype "passive"))
      (node (ref "J15") (pin "83") (pinfunction "83_83") (pintype "passive"))
      (node (ref "J15") (pin "97") (pinfunction "97_97") (pintype "passive"))
      (node (ref "J16") (pin "10") (pinfunction "10_10") (pintype "power_in"))
      (node (ref "J16") (pin "12") (pinfunction "12_12") (pintype "power_in"))
      (node (ref "J16") (pin "14") (pinfunction "14_14") (pintype "power_in"))
      (node (ref "J16") (pin "16") (pinfunction "16_16") (pintype "power_in"))
      (node (ref "J16") (pin "18") (pinfunction "18_18") (pintype "power_in"))
      (node (ref "J16") (pin "20") (pinfunction "20_20") (pintype "power_in"))
      (node (ref "J16") (pin "22") (pinfunction "22_22") (pintype "power_in"))
      (node (ref "J16") (pin "27") (pinfunction "27_27") (pintype "power_in"))
      (node (ref "J16") (pin "37") (pinfunction "37_37") (pintype "power_in"))
      (node (ref "J16") (pin "47") (pinfunction "47_47") (pintype "power_in"))
      (node (ref "J16") (pin "58") (pinfunction "58_58") (pintype "power_in"))
      (node (ref "J16") (pin "60") (pinfunction "60_60") (pintype "power_in"))
      (node (ref "J16") (pin "62") (pinfunction "62_62") (pintype "power_in"))
      (node (ref "J16") (pin "64") (pinfunction "64_64") (pintype "power_in"))
      (node (ref "J16") (pin "66") (pinfunction "66_66") (pintype "power_in"))
      (node (ref "J16") (pin "68") (pinfunction "68_68") (pintype "power_in"))
      (node (ref "J16") (pin "70") (pinfunction "70_70") (pintype "power_in"))
      (node (ref "J16") (pin "72") (pinfunction "72_72") (pintype "power_in"))
      (node (ref "J16") (pin "8") (pinfunction "8_8") (pintype "power_in"))
      (node (ref "J26") (pin "15") (pinfunction "15_15") (pintype "passive"))
      (node (ref "J26") (pin "37") (pinfunction "37_37") (pintype "passive"))
      (node (ref "J26") (pin "59") (pinfunction "59_59") (pintype "passive"))
      (node (ref "P14") (pin "10") (pinfunction "10_10") (pintype "passive"))
      (node (ref "P14") (pin "12") (pinfunction "12_12") (pintype "passive"))
      (node (ref "P14") (pin "4") (pinfunction "4_4") (pintype "passive"))
      (node (ref "P14") (pin "8") (pinfunction "8_8") (pintype "passive"))
      (node (ref "P15") (pin "10") (pinfunction "10_10") (pintype "passive"))
      (node (ref "P16") (pin "10") (pinfunction "10_10") (pintype "passive"))
      (node (ref "P17") (pin "3") (pinfunction "3_3") (pintype "passive"))
      (node (ref "P18") (pin "3") (pinfunction "3_3") (pintype "passive"))
      (node (ref "U8") (pin "2") (pinfunction "GND_2") (pintype "power_in"))
      (node (ref "U9") (pin "2") (pinfunction "GND_2") (pintype "power_in"))
    )
    (net (code "219") (name "unconnected-(J15-Pad1)") (class "Default")
      (node (ref "J15") (pin "1") (pinfunction "1_1") (pintype "passive"))
    )
    (net (code "220") (name "unconnected-(J15-Pad2)") (class "Default")
      (node (ref "J15") (pin "2") (pinfunction "2_2") (pintype "passive"))
    )
    (net (code "221") (name "unconnected-(J15-Pad3)") (class "Default")
      (node (ref "J15") (pin "3") (pinfunction "3_3") (pintype "passive"))
    )
    (net (code "222") (name "unconnected-(J15-Pad4)") (class "Default")
      (node (ref "J15") (pin "4") (pinfunction "4_4") (pintype "passive"))
    )
    (net (code "223") (name "unconnected-(J15-Pad5)") (class "Default")
      (node (ref "J15") (pin "5") (pinfunction "5_5") (pintype "passive"))
    )
    (net (code "224") (name "unconnected-(J15-Pad6)") (class "Default")
      (node (ref "J15") (pin "6") (pinfunction "6_6") (pintype "passive"))
    )
    (net (code "225") (name "unconnected-(J15-Pad8)") (class "Default")
      (node (ref "J15") (pin "8") (pinfunction "8_8") (pintype "passive"))
    )
    (net (code "226") (name "unconnected-(J15-Pad13)") (class "Default")
      (node (ref "J15") (pin "13") (pinfunction "13_13") (pintype "passive"))
    )
    (net (code "227") (name "unconnected-(J15-Pad16)") (class "Default")
      (node (ref "J15") (pin "16") (pinfunction "16_16") (pintype "passive"))
    )
    (net (code "228") (name "unconnected-(J15-Pad29)") (class "Default")
      (node (ref "J15") (pin "29") (pinfunction "29_29") (pintype "passive"))
    )
    (net (code "229") (name "unconnected-(J15-Pad32)") (class "Default")
      (node (ref "J15") (pin "32") (pinfunction "32_32") (pintype "passive"))
    )
    (net (code "230") (name "unconnected-(J15-Pad41)") (class "Default")
      (node (ref "J15") (pin "41") (pinfunction "41_41") (pintype "passive"))
    )
    (net (code "231") (name "unconnected-(J15-Pad43)") (class "Default")
      (node (ref "J15") (pin "43") (pinfunction "43_43") (pintype "passive"))
    )
    (net (code "232") (name "unconnected-(J15-Pad44)") (class "Default")
      (node (ref "J15") (pin "44") (pinfunction "44_44") (pintype "passive"))
    )
    (net (code "233") (name "unconnected-(J15-Pad45)") (class "Default")
      (node (ref "J15") (pin "45") (pinfunction "45_45") (pintype "passive"))
    )
    (net (code "234") (name "unconnected-(J15-Pad66)") (class "Default")
      (node (ref "J15") (pin "66") (pinfunction "66_66") (pintype "passive"))
    )
    (net (code "235") (name "unconnected-(J15-Pad75)") (class "Default")
      (node (ref "J15") (pin "75") (pinfunction "75_75") (pintype "passive"))
    )
    (net (code "236") (name "unconnected-(J15-Pad77)") (class "Default")
      (node (ref "J15") (pin "77") (pinfunction "77_77") (pintype "passive"))
    )
    (net (code "237") (name "unconnected-(J15-Pad79)") (class "Default")
      (node (ref "J15") (pin "79") (pinfunction "79_79") (pintype "passive"))
    )
    (net (code "238") (name "unconnected-(J15-Pad80)") (class "Default")
      (node (ref "J15") (pin "80") (pinfunction "80_80") (pintype "passive"))
    )
    (net (code "239") (name "unconnected-(J15-Pad81)") (class "Default")
      (node (ref "J15") (pin "81") (pinfunction "81_81") (pintype "passive"))
    )
    (net (code "240") (name "unconnected-(J15-Pad82)") (class "Default")
      (node (ref "J15") (pin "82") (pinfunction "82_82") (pintype "passive"))
    )
    (net (code "241") (name "unconnected-(J15-Pad86)") (class "Default")
      (node (ref "J15") (pin "86") (pinfunction "86_86") (pintype "passive"))
    )
    (net (code "242") (name "unconnected-(J15-Pad89)") (class "Default")
      (node (ref "J15") (pin "89") (pinfunction "89_89") (pintype "passive"))
    )
    (net (code "243") (name "unconnected-(J15-Pad91)") (class "Default")
      (node (ref "J15") (pin "91") (pinfunction "91_91") (pintype "passive"))
    )
    (net (code "244") (name "unconnected-(J15-Pad92)") (class "Default")
      (node (ref "J15") (pin "92") (pinfunction "92_92") (pintype "passive"))
    )
    (net (code "245") (name "unconnected-(J15-Pad93)") (class "Default")
      (node (ref "J15") (pin "93") (pinfunction "93_93") (pintype "passive"))
    )
    (net (code "246") (name "unconnected-(J15-Pad94)") (class "Default")
      (node (ref "J15") (pin "94") (pinfunction "94_94") (pintype "passive"))
    )
    (net (code "247") (name "unconnected-(J15-Pad95)") (class "Default")
      (node (ref "J15") (pin "95") (pinfunction "95_95") (pintype "passive"))
    )
    (net (code "248") (name "unconnected-(J15-Pad96)") (class "Default")
      (node (ref "J15") (pin "96") (pinfunction "96_96") (pintype "passive"))
    )
    (net (code "249") (name "unconnected-(J15-Pad99)") (class "Default")
      (node (ref "J15") (pin "99") (pinfunction "99_99") (pintype "passive"))
    )
    (net (code "250") (name "unconnected-(J15-Pad100)") (class "Default")
      (node (ref "J15") (pin "100") (pinfunction "100_100") (pintype "passive"))
    )
    (net (code "251") (name "unconnected-(J15-Pad101)") (class "Default")
      (node (ref "J15") (pin "101") (pinfunction "101_101") (pintype "passive"))
    )
    (net (code "252") (name "unconnected-(J15-Pad102)") (class "Default")
      (node (ref "J15") (pin "102") (pinfunction "102_102") (pintype "passive"))
    )
    (net (code "253") (name "unconnected-(J15-Pad103)") (class "Default")
      (node (ref "J15") (pin "103") (pinfunction "103_103") (pintype "passive"))
    )
    (net (code "254") (name "unconnected-(J15-Pad104)") (class "Default")
      (node (ref "J15") (pin "104") (pinfunction "104_104") (pintype "passive"))
    )
    (net (code "255") (name "unconnected-(J15-Pad105)") (class "Default")
      (node (ref "J15") (pin "105") (pinfunction "105_105") (pintype "passive"))
    )
    (net (code "256") (name "unconnected-(J15-Pad106)") (class "Default")
      (node (ref "J15") (pin "106") (pinfunction "106_106") (pintype "passive"))
    )
    (net (code "257") (name "unconnected-(J15-Pad107)") (class "Default")
      (node (ref "J15") (pin "107") (pinfunction "107_107") (pintype "passive"))
    )
    (net (code "258") (name "unconnected-(J15-Pad108)") (class "Default")
      (node (ref "J15") (pin "108") (pinfunction "108_108") (pintype "passive"))
    )
    (net (code "259") (name "unconnected-(J15-Pad109)") (class "Default")
      (node (ref "J15") (pin "109") (pinfunction "109_109") (pintype "passive"))
    )
    (net (code "260") (name "unconnected-(J15-Pad110)") (class "Default")
      (node (ref "J15") (pin "110") (pinfunction "110_110") (pintype "passive"))
    )
    (net (code "261") (name "unconnected-(J15-Pad113)") (class "Default")
      (node (ref "J15") (pin "113") (pinfunction "113_113") (pintype "passive"))
    )
    (net (code "262") (name "unconnected-(J15-Pad114)") (class "Default")
      (node (ref "J15") (pin "114") (pinfunction "114_114") (pintype "passive"))
    )
    (net (code "263") (name "unconnected-(J15-Pad115)") (class "Default")
      (node (ref "J15") (pin "115") (pinfunction "115_115") (pintype "passive"))
    )
    (net (code "264") (name "unconnected-(J15-Pad116)") (class "Default")
      (node (ref "J15") (pin "116") (pinfunction "116_116") (pintype "passive"))
    )
    (net (code "265") (name "unconnected-(J15-Pad117)") (class "Default")
      (node (ref "J15") (pin "117") (pinfunction "117_117") (pintype "passive"))
    )
    (net (code "266") (name "unconnected-(J15-Pad118)") (class "Default")
      (node (ref "J15") (pin "118") (pinfunction "118_118") (pintype "passive"))
    )
    (net (code "267") (name "unconnected-(J15-Pad119)") (class "Default")
      (node (ref "J15") (pin "119") (pinfunction "119_119") (pintype "passive"))
    )
    (net (code "268") (name "unconnected-(J15-Pad120)") (class "Default")
      (node (ref "J15") (pin "120") (pinfunction "120_120") (pintype "passive"))
    )
    (net (code "269") (name "unconnected-(J15-Pad121)") (class "Default")
      (node (ref "J15") (pin "121") (pinfunction "121_121") (pintype "passive"))
    )
    (net (code "270") (name "unconnected-(J15-Pad122)") (class "Default")
      (node (ref "J15") (pin "122") (pinfunction "122_122") (pintype "passive"))
    )
    (net (code "271") (name "unconnected-(J16-Pad1)") (class "Default")
      (node (ref "J16") (pin "1") (pinfunction "1_1") (pintype "power_in"))
    )
    (net (code "272") (name "unconnected-(J16-Pad2)") (class "Default")
      (node (ref "J16") (pin "2") (pinfunction "2_2") (pintype "power_in"))
    )
    (net (code "273") (name "unconnected-(J16-Pad3)") (class "Default")
      (node (ref "J16") (pin "3") (pinfunction "3_3") (pintype "power_in"))
    )
    (net (code "274") (name "unconnected-(J16-Pad4)") (class "Default")
      (node (ref "J16") (pin "4") (pinfunction "4_4") (pintype "power_in"))
    )
    (net (code "275") (name "unconnected-(J16-Pad5)") (class "Default")
      (node (ref "J16") (pin "5") (pinfunction "5_5") (pintype "power_in"))
    )
    (net (code "276") (name "unconnected-(J16-Pad6)") (class "Default")
      (node (ref "J16") (pin "6") (pinfunction "6_6") (pintype "power_in"))
    )
    (net (code "277") (name "unconnected-(J16-Pad31)") (class "Default")
      (node (ref "J16") (pin "31") (pinfunction "31_31") (pintype "power_in"))
    )
    (net (code "278") (name "unconnected-(J16-Pad32)") (class "Default")
      (node (ref "J16") (pin "32") (pinfunction "32_32") (pintype "power_in"))
    )
    (net (code "279") (name "unconnected-(J16-Pad41)") (class "Default")
      (node (ref "J16") (pin "41") (pinfunction "41_41") (pintype "power_in"))
    )
    (net (code "280") (name "unconnected-(J16-Pad42)") (class "Default")
      (node (ref "J16") (pin "42") (pinfunction "42_42") (pintype "power_in"))
    )
    (net (code "281") (name "unconnected-(J16-Pad44)") (class "Default")
      (node (ref "J16") (pin "44") (pinfunction "44_44") (pintype "power_in"))
    )
    (net (code "282") (name "unconnected-(J16-Pad46)") (class "Default")
      (node (ref "J16") (pin "46") (pinfunction "46_46") (pintype "power_in"))
    )
    (net (code "283") (name "unconnected-(J16-Pad51)") (class "Default")
      (node (ref "J16") (pin "51") (pinfunction "51_51") (pintype "power_in"))
    )
    (net (code "284") (name "unconnected-(J16-Pad52)") (class "Default")
      (node (ref "J16") (pin "52") (pinfunction "52_52") (pintype "power_in"))
    )
    (net (code "285") (name "unconnected-(J16-Pad53)") (class "Default")
      (node (ref "J16") (pin "53") (pinfunction "53_53") (pintype "power_in"))
    )
    (net (code "286") (name "unconnected-(J16-Pad54)") (class "Default")
      (node (ref "J16") (pin "54") (pinfunction "54_54") (pintype "power_in"))
    )
    (net (code "287") (name "unconnected-(J16-Pad55)") (class "Default")
      (node (ref "J16") (pin "55") (pinfunction "55_55") (pintype "power_in"))
    )
    (net (code "288") (name "unconnected-(J16-Pad56)") (class "Default")
      (node (ref "J16") (pin "56") (pinfunction "56_56") (pintype "power_in"))
    )
    (net (code "289") (name "unconnected-(J16-Pad81)") (class "Default")
      (node (ref "J16") (pin "81") (pinfunction "81_81") (pintype "power_in"))
    )
    (net (code "290") (name "unconnected-(J16-Pad86)") (class "Default")
      (node (ref "J16") (pin "86") (pinfunction "86_86") (pintype "power_in"))
    )
    (net (code "291") (name "unconnected-(J16-Pad94)") (class "Default")
      (node (ref "J16") (pin "94") (pinfunction "94_94") (pintype "power_in"))
    )
    (net (code "292") (name "unconnected-(J26-Pad16)") (class "Default")
      (node (ref "J26") (pin "16") (pinfunction "16_16") (pintype "passive"))
    )
    (net (code "293") (name "unconnected-(J26-Pad51)") (class "Default")
      (node (ref "J26") (pin "51") (pinfunction "51_51") (pintype "passive"))
    )
    (net (code "294") (name "unconnected-(J26-Pad52)") (class "Default")
      (node (ref "J26") (pin "52") (pinfunction "52_52") (pintype "passive"))
    )
    (net (code "295") (name "unconnected-(J26-Pad53)") (class "Default")
      (node (ref "J26") (pin "53") (pinfunction "53_53") (pintype "passive"))
    )
    (net (code "296") (name "unconnected-(J26-Pad54)") (class "Default")
      (node (ref "J26") (pin "54") (pinfunction "54_54") (pintype "passive"))
    )
    (net (code "297") (name "unconnected-(J26-Pad55)") (class "Default")
      (node (ref "J26") (pin "55") (pinfunction "55_55") (pintype "passive"))
    )
    (net (code "298") (name "unconnected-(J26-Pad56)") (class "Default")
      (node (ref "J26") (pin "56") (pinfunction "56_56") (pintype "passive"))
    )
    (net (code "299") (name "unconnected-(J26-Pad57)") (class "Default")
      (node (ref "J26") (pin "57") (pinfunction "57_57") (pintype "passive"))
    )
    (net (code "300") (name "unconnected-(J26-Pad58)") (class "Default")
      (node (ref "J26") (pin "58") (pinfunction "58_58") (pintype "passive"))
    )
    (net (code "301") (name "unconnected-(J26-Pad61)") (class "Default")
      (node (ref "J26") (pin "61") (pinfunction "61_61") (pintype "passive"))
    )
    (net (code "302") (name "unconnected-(J26-Pad62)") (class "Default")
      (node (ref "J26") (pin "62") (pinfunction "62_62") (pintype "passive"))
    )
    (net (code "303") (name "unconnected-(P14-Pad5)") (class "Default")
      (node (ref "P14") (pin "5") (pinfunction "5_5") (pintype "passive"))
    )
    (net (code "304") (name "unconnected-(P14-Pad6)") (class "Default")
      (node (ref "P14") (pin "6") (pinfunction "6_6") (pintype "passive"))
    )
    (net (code "305") (name "unconnected-(P15-Pad1)") (class "Default")
      (node (ref "P15") (pin "1") (pinfunction "1_1") (pintype "passive"))
    )
    (net (code "306") (name "unconnected-(P15-Pad2)") (class "Default")
      (node (ref "P15") (pin "2") (pinfunction "2_2") (pintype "passive"))
    )
    (net (code "307") (name "unconnected-(P16-Pad1)") (class "Default")
      (node (ref "P16") (pin "1") (pinfunction "1_1") (pintype "passive"))
    )
    (net (code "308") (name "unconnected-(P16-Pad2)") (class "Default")
      (node (ref "P16") (pin "2") (pinfunction "2_2") (pintype "passive"))
    )
    (net (code "309") (name "unconnected-(U8-NC-Pad4)") (class "Default")
      (node (ref "U8") (pin "4") (pinfunction "NC_4") (pintype "passive"))
    )
    (net (code "310") (name "unconnected-(U9-NC-Pad4)") (class "Default")
      (node (ref "U9") (pin "4") (pinfunction "NC_4") (pintype "passive"))
    )
  )
)
